# Sheet1.net
KiCad netlist of a schematic drawn in Altium Designer
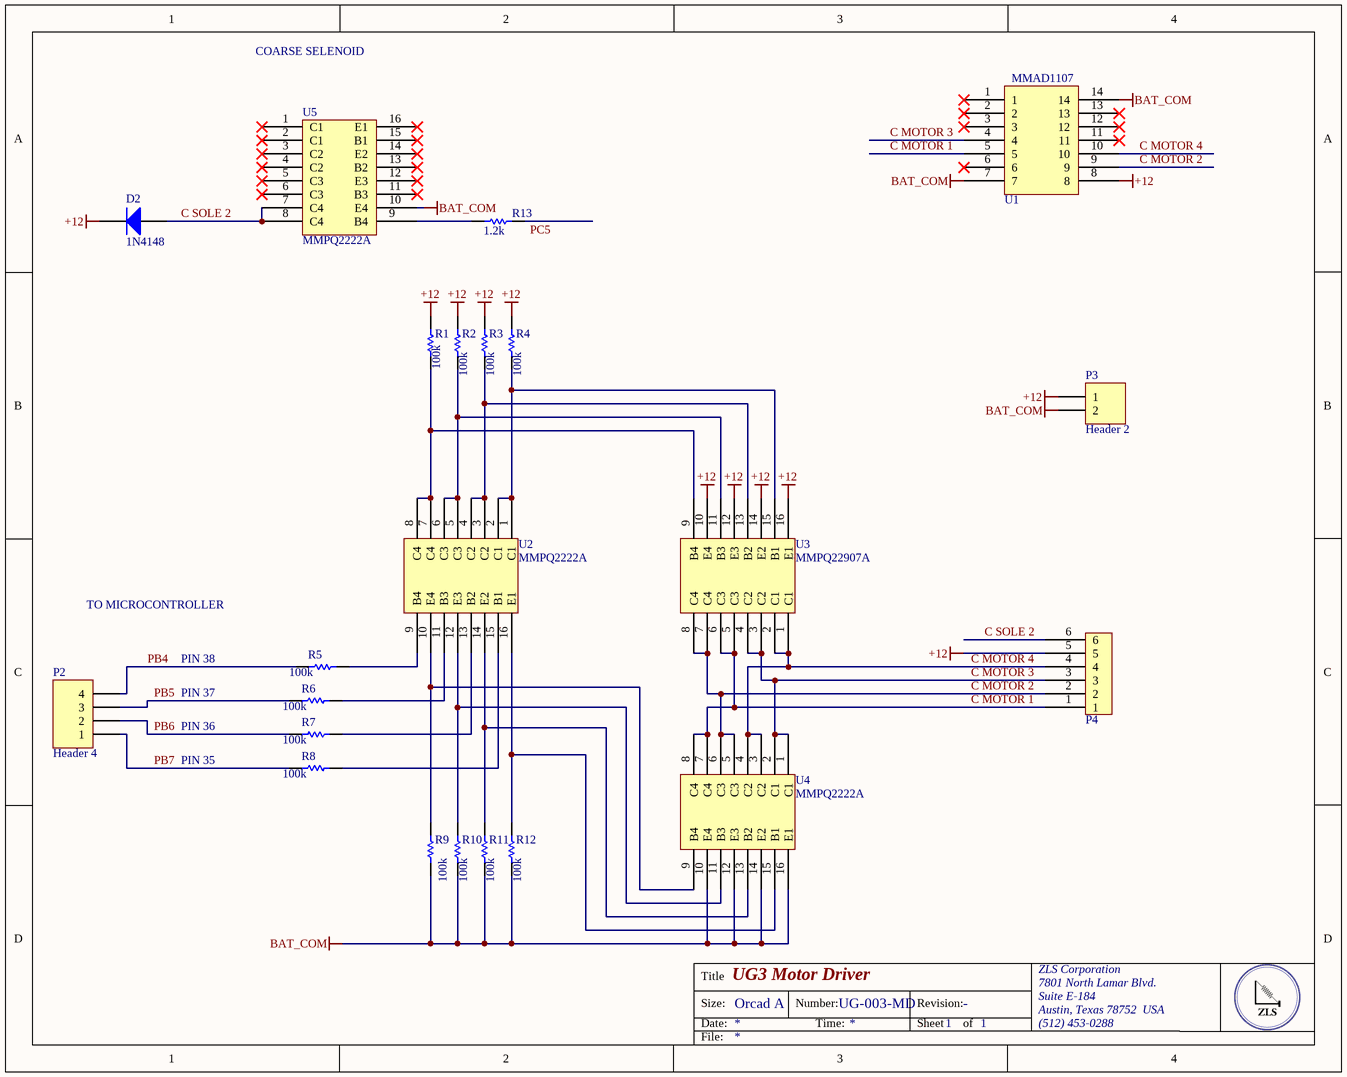
[diagram p0: Sheet1.SchDoc]

(export (version "E")
  (design (tool "Eeschema 10.0.6"))
  (components
    (comp (ref "D2")
      (value "1N4148")
      (footprint "NXP-SOD27-2_V")
      (description "High-speed Diode, 100 V, 450 mA, 2-Pin SOD27, RoHS")
      (fields (field (name "MANUFACTURER") "NXP Semiconductors"))
      (libsource (lib "Altium Content Vault") (part "NXP-A1K2-2"))
    )
    (comp (ref "P2")
      (value "Header 4")
      (footprint "HDR1X4")
      (description "Header, 4-Pin")
      (fields (field (name "PUBLISHER") "Altium Limited"))
      (libsource (lib "Miscellaneous Connectors") (part "Header 4"))
    )
    (comp (ref "P3")
      (value "Header 2")
      (footprint "HDR1X2")
      (description "Header, 2-Pin")
      (fields (field (name "PUBLISHER") "Altium Limited"))
      (libsource (lib "Miscellaneous Connectors") (part "Header 2"))
    )
    (comp (ref "P4") (value "JF-6") (footprint "JF-6") (libsource (lib "ZLS_Schematic_lib") (part "JF-6")))
    (comp (ref "R1")
      (value "100k")
      (footprint "RESC0805(2012)_L")
      (description "2R55 0.125W 1% 0805 (2012 Metric)  SMD")
      (fields (field (name "TOLERANCE") "1 %") (field (name "POWER") "0.125 W"))
      (libsource (lib "Altium Content Vault") (part "CMP-1013-00215-1"))
    )
    (comp (ref "R2")
      (value "100k")
      (footprint "RESC0805(2012)_L")
      (description "2R55 0.125W 1% 0805 (2012 Metric)  SMD")
      (fields (field (name "TOLERANCE") "1 %") (field (name "POWER") "0.125 W"))
      (libsource (lib "Altium Content Vault") (part "CMP-1013-00215-1"))
    )
    (comp (ref "R3")
      (value "100k")
      (footprint "RESC0805(2012)_L")
      (description "2R55 0.125W 1% 0805 (2012 Metric)  SMD")
      (fields (field (name "TOLERANCE") "1 %") (field (name "POWER") "0.125 W"))
      (libsource (lib "Altium Content Vault") (part "CMP-1013-00215-1"))
    )
    (comp (ref "R4")
      (value "100k")
      (footprint "RESC0805(2012)_L")
      (description "2R55 0.125W 1% 0805 (2012 Metric)  SMD")
      (fields (field (name "TOLERANCE") "1 %") (field (name "POWER") "0.125 W"))
      (libsource (lib "Altium Content Vault") (part "CMP-1013-00215-1"))
    )
    (comp (ref "R5")
      (value "100k")
      (footprint "RESC0805(2012)_L")
      (description "2R55 0.125W 1% 0805 (2012 Metric)  SMD")
      (fields (field (name "TOLERANCE") "1 %") (field (name "POWER") "0.125 W"))
      (libsource (lib "Altium Content Vault") (part "CMP-1013-00215-1"))
    )
    (comp (ref "R6")
      (value "100k")
      (footprint "RESC0805(2012)_L")
      (description "2R55 0.125W 1% 0805 (2012 Metric)  SMD")
      (fields (field (name "TOLERANCE") "1 %") (field (name "POWER") "0.125 W"))
      (libsource (lib "Altium Content Vault") (part "CMP-1013-00215-1"))
    )
    (comp (ref "R7")
      (value "100k")
      (footprint "RESC0805(2012)_L")
      (description "2R55 0.125W 1% 0805 (2012 Metric)  SMD")
      (fields (field (name "TOLERANCE") "1 %") (field (name "POWER") "0.125 W"))
      (libsource (lib "Altium Content Vault") (part "CMP-1013-00215-1"))
    )
    (comp (ref "R8")
      (value "100k")
      (footprint "RESC0805(2012)_L")
      (description "2R55 0.125W 1% 0805 (2012 Metric)  SMD")
      (fields (field (name "TOLERANCE") "1 %") (field (name "POWER") "0.125 W"))
      (libsource (lib "Altium Content Vault") (part "CMP-1013-00215-1"))
    )
    (comp (ref "R9")
      (value "100k")
      (footprint "RESC0805(2012)_L")
      (description "2R55 0.125W 1% 0805 (2012 Metric)  SMD")
      (fields (field (name "TOLERANCE") "1 %") (field (name "POWER") "0.125 W"))
      (libsource (lib "Altium Content Vault") (part "CMP-1013-00215-1"))
    )
    (comp (ref "R10")
      (value "100k")
      (footprint "RESC0805(2012)_L")
      (description "2R55 0.125W 1% 0805 (2012 Metric)  SMD")
      (fields (field (name "TOLERANCE") "1 %") (field (name "POWER") "0.125 W"))
      (libsource (lib "Altium Content Vault") (part "CMP-1013-00215-1"))
    )
    (comp (ref "R11")
      (value "100k")
      (footprint "RESC0805(2012)_L")
      (description "2R55 0.125W 1% 0805 (2012 Metric)  SMD")
      (fields (field (name "TOLERANCE") "1 %") (field (name "POWER") "0.125 W"))
      (libsource (lib "Altium Content Vault") (part "CMP-1013-00215-1"))
    )
    (comp (ref "R12")
      (value "100k")
      (footprint "RESC0805(2012)_L")
      (description "2R55 0.125W 1% 0805 (2012 Metric)  SMD")
      (fields (field (name "TOLERANCE") "1 %") (field (name "POWER") "0.125 W"))
      (libsource (lib "Altium Content Vault") (part "CMP-1013-00215-1"))
    )
    (comp (ref "R13")
      (value "1.2k")
      (footprint "RESC0805(2012)_L")
      (description "2R55 0.125W 1% 0805 (2012 Metric)  SMD")
      (fields (field (name "TOLERANCE") "1 %") (field (name "POWER") "0.125 W"))
      (libsource (lib "Altium Content Vault") (part "CMP-1013-00215-1"))
    )
    (comp (ref "U1")
      (value "MMAD1107")
      (footprint "MMAD1107")
      (libsource (lib "ZLS_Schematic_lib") (part "MMAD1107"))
    )
    (comp (ref "U2")
      (value "MMPQ2222A")
      (footprint "MMPQ2222A")
      (libsource (lib "ZLS_Schematic_lib") (part "MMPQ2222A"))
    )
    (comp (ref "U3")
      (value "MMPQ22907A")
      (footprint "MMPQ22907A")
      (libsource (lib "ZLS_Schematic_lib") (part "MMPQ22907A"))
    )
    (comp (ref "U4")
      (value "MMPQ2222A")
      (footprint "MMPQ2222A")
      (libsource (lib "ZLS_Schematic_lib") (part "MMPQ2222A"))
    )
    (comp (ref "U5") (value "MMPQ2222A") (footprint "MMPQ2222A") (libsource (lib "") (part "MMPQ2222A_1")))
  )
  (nets
    (net (code "1") (name "+12") (class "Default")
      (node (ref "D2") (pin "2") (pinfunction "K_2") (pintype "passive"))
      (node (ref "P3") (pin "1") (pinfunction "1_1") (pintype "passive"))
      (node (ref "P4") (pin "5") (pinfunction "5_5") (pintype "passive"))
      (node (ref "R1") (pin "1") (pinfunction "1_1") (pintype "passive"))
      (node (ref "R2") (pin "1") (pinfunction "1_1") (pintype "passive"))
      (node (ref "R3") (pin "1") (pinfunction "1_1") (pintype "passive"))
      (node (ref "R4") (pin "1") (pinfunction "1_1") (pintype "passive"))
      (node (ref "U1") (pin "8") (pinfunction "8_8") (pintype "passive"))
      (node (ref "U3") (pin "10") (pinfunction "E4_10") (pintype "passive"))
      (node (ref "U3") (pin "12") (pinfunction "E3_12") (pintype "passive"))
      (node (ref "U3") (pin "14") (pinfunction "E2_14") (pintype "passive"))
      (node (ref "U3") (pin "16") (pinfunction "E1_16") (pintype "passive"))
    )
    (net (code "2") (name "/C MOTOR 1") (class "Default")
      (node (ref "P4") (pin "1") (pinfunction "1_1") (pintype "passive"))
      (node (ref "U1") (pin "5") (pinfunction "5_5") (pintype "passive"))
      (node (ref "U3") (pin "5") (pinfunction "C3_5") (pintype "passive"))
      (node (ref "U3") (pin "6") (pinfunction "C3_6") (pintype "passive"))
      (node (ref "U4") (pin "7") (pinfunction "C4_7") (pintype "passive"))
      (node (ref "U4") (pin "8") (pinfunction "C4_8") (pintype "passive"))
    )
    (net (code "3") (name "/C MOTOR 2") (class "Default")
      (node (ref "P4") (pin "2") (pinfunction "2_2") (pintype "passive"))
      (node (ref "U1") (pin "9") (pinfunction "9_9") (pintype "passive"))
      (node (ref "U3") (pin "7") (pinfunction "C4_7") (pintype "passive"))
      (node (ref "U3") (pin "8") (pinfunction "C4_8") (pintype "passive"))
      (node (ref "U4") (pin "5") (pinfunction "C3_5") (pintype "passive"))
      (node (ref "U4") (pin "6") (pinfunction "C3_6") (pintype "passive"))
    )
    (net (code "4") (name "/C MOTOR 3") (class "Default")
      (node (ref "P4") (pin "3") (pinfunction "3_3") (pintype "passive"))
      (node (ref "U1") (pin "4") (pinfunction "4_4") (pintype "passive"))
      (node (ref "U3") (pin "3") (pinfunction "C2_3") (pintype "passive"))
      (node (ref "U3") (pin "4") (pinfunction "C2_4") (pintype "passive"))
      (node (ref "U4") (pin "1") (pinfunction "C1_1") (pintype "passive"))
      (node (ref "U4") (pin "2") (pinfunction "C1_2") (pintype "passive"))
    )
    (net (code "5") (name "/C MOTOR 4") (class "Default")
      (node (ref "P4") (pin "4") (pinfunction "4_4") (pintype "passive"))
      (node (ref "U1") (pin "10") (pinfunction "10_10") (pintype "passive"))
      (node (ref "U3") (pin "1") (pinfunction "C1_1") (pintype "passive"))
      (node (ref "U3") (pin "2") (pinfunction "C1_2") (pintype "passive"))
      (node (ref "U4") (pin "3") (pinfunction "C2_3") (pintype "passive"))
      (node (ref "U4") (pin "4") (pinfunction "C2_4") (pintype "passive"))
    )
    (net (code "6") (name "/C SOLE 2") (class "Default")
      (node (ref "D2") (pin "1") (pinfunction "A_1") (pintype "passive"))
      (node (ref "P4") (pin "6") (pinfunction "6_6") (pintype "passive"))
      (node (ref "U5") (pin "7") (pinfunction "C4_7") (pintype "passive"))
      (node (ref "U5") (pin "8") (pinfunction "C4_8") (pintype "passive"))
    )
    (net (code "7") (name "/PB4") (class "Default")
      (node (ref "P2") (pin "4") (pinfunction "4_4") (pintype "passive"))
      (node (ref "R5") (pin "2") (pinfunction "2_2") (pintype "passive"))
    )
    (net (code "8") (name "/PB5") (class "Default")
      (node (ref "P2") (pin "3") (pinfunction "3_3") (pintype "passive"))
      (node (ref "R6") (pin "2") (pinfunction "2_2") (pintype "passive"))
    )
    (net (code "9") (name "/PB6") (class "Default")
      (node (ref "P2") (pin "2") (pinfunction "2_2") (pintype "passive"))
      (node (ref "R7") (pin "2") (pinfunction "2_2") (pintype "passive"))
    )
    (net (code "10") (name "/PB7") (class "Default")
      (node (ref "P2") (pin "1") (pinfunction "1_1") (pintype "passive"))
      (node (ref "R8") (pin "2") (pinfunction "2_2") (pintype "passive"))
    )
    (net (code "11") (name "/PC5") (class "Default")
      (node (ref "R13") (pin "2") (pinfunction "2_2") (pintype "passive"))
    )
    (net (code "12") (name "BAT_COM") (class "Default")
      (node (ref "P3") (pin "2") (pinfunction "2_2") (pintype "passive"))
      (node (ref "R10") (pin "1") (pinfunction "1_1") (pintype "passive"))
      (node (ref "R11") (pin "1") (pinfunction "1_1") (pintype "passive"))
      (node (ref "R12") (pin "1") (pinfunction "1_1") (pintype "passive"))
      (node (ref "R9") (pin "1") (pinfunction "1_1") (pintype "passive"))
      (node (ref "U1") (pin "14") (pinfunction "14_14") (pintype "passive"))
      (node (ref "U1") (pin "7") (pinfunction "7_7") (pintype "passive"))
      (node (ref "U4") (pin "10") (pinfunction "E4_10") (pintype "passive"))
      (node (ref "U4") (pin "12") (pinfunction "E3_12") (pintype "passive"))
      (node (ref "U4") (pin "14") (pinfunction "E2_14") (pintype "passive"))
      (node (ref "U4") (pin "16") (pinfunction "E1_16") (pintype "passive"))
      (node (ref "U5") (pin "10") (pinfunction "E4_10") (pintype "passive"))
    )
    (net (code "13") (name "Net-(U2-B1)") (class "Default")
      (node (ref "R8") (pin "1") (pinfunction "1_1") (pintype "passive"))
      (node (ref "U2") (pin "15") (pinfunction "B1_15") (pintype "passive"))
    )
    (net (code "14") (name "Net-(U2-B2)") (class "Default")
      (node (ref "R7") (pin "1") (pinfunction "1_1") (pintype "passive"))
      (node (ref "U2") (pin "13") (pinfunction "B2_13") (pintype "passive"))
    )
    (net (code "15") (name "Net-(U2-B3)") (class "Default")
      (node (ref "R6") (pin "1") (pinfunction "1_1") (pintype "passive"))
      (node (ref "U2") (pin "11") (pinfunction "B3_11") (pintype "passive"))
    )
    (net (code "16") (name "Net-(U2-B4)") (class "Default")
      (node (ref "R5") (pin "1") (pinfunction "1_1") (pintype "passive"))
      (node (ref "U2") (pin "9") (pinfunction "B4_9") (pintype "passive"))
    )
    (net (code "17") (name "Net-(U2-E1)") (class "Default")
      (node (ref "R12") (pin "2") (pinfunction "2_2") (pintype "passive"))
      (node (ref "U2") (pin "16") (pinfunction "E1_16") (pintype "passive"))
      (node (ref "U4") (pin "15") (pinfunction "B1_15") (pintype "passive"))
    )
    (net (code "18") (name "Net-(U2-E2)") (class "Default")
      (node (ref "R11") (pin "2") (pinfunction "2_2") (pintype "passive"))
      (node (ref "U2") (pin "14") (pinfunction "E2_14") (pintype "passive"))
      (node (ref "U4") (pin "13") (pinfunction "B2_13") (pintype "passive"))
    )
    (net (code "19") (name "Net-(U2-E3)") (class "Default")
      (node (ref "R10") (pin "2") (pinfunction "2_2") (pintype "passive"))
      (node (ref "U2") (pin "12") (pinfunction "E3_12") (pintype "passive"))
      (node (ref "U4") (pin "11") (pinfunction "B3_11") (pintype "passive"))
    )
    (net (code "20") (name "Net-(U2-E4)") (class "Default")
      (node (ref "R9") (pin "2") (pinfunction "2_2") (pintype "passive"))
      (node (ref "U2") (pin "10") (pinfunction "E4_10") (pintype "passive"))
      (node (ref "U4") (pin "9") (pinfunction "B4_9") (pintype "passive"))
    )
    (net (code "21") (name "Net-(U3-B1)") (class "Default")
      (node (ref "R4") (pin "2") (pinfunction "2_2") (pintype "passive"))
      (node (ref "U2") (pin "1") (pinfunction "C1_1") (pintype "passive"))
      (node (ref "U2") (pin "2") (pinfunction "C1_2") (pintype "passive"))
      (node (ref "U3") (pin "15") (pinfunction "B1_15") (pintype "passive"))
    )
    (net (code "22") (name "Net-(U3-B2)") (class "Default")
      (node (ref "R3") (pin "2") (pinfunction "2_2") (pintype "passive"))
      (node (ref "U2") (pin "3") (pinfunction "C2_3") (pintype "passive"))
      (node (ref "U2") (pin "4") (pinfunction "C2_4") (pintype "passive"))
      (node (ref "U3") (pin "13") (pinfunction "B2_13") (pintype "passive"))
    )
    (net (code "23") (name "Net-(U3-B3)") (class "Default")
      (node (ref "R2") (pin "2") (pinfunction "2_2") (pintype "passive"))
      (node (ref "U2") (pin "5") (pinfunction "C3_5") (pintype "passive"))
      (node (ref "U2") (pin "6") (pinfunction "C3_6") (pintype "passive"))
      (node (ref "U3") (pin "11") (pinfunction "B3_11") (pintype "passive"))
    )
    (net (code "24") (name "Net-(U3-B4)") (class "Default")
      (node (ref "R1") (pin "2") (pinfunction "2_2") (pintype "passive"))
      (node (ref "U2") (pin "7") (pinfunction "C4_7") (pintype "passive"))
      (node (ref "U2") (pin "8") (pinfunction "C4_8") (pintype "passive"))
      (node (ref "U3") (pin "9") (pinfunction "B4_9") (pintype "passive"))
    )
    (net (code "25") (name "Net-(U5-B4)") (class "Default")
      (node (ref "R13") (pin "1") (pinfunction "1_1") (pintype "passive"))
      (node (ref "U5") (pin "9") (pinfunction "B4_9") (pintype "passive"))
    )
    (net (code "26") (name "unconnected-(U1-Pad1)") (class "Default")
      (node (ref "U1") (pin "1") (pinfunction "1_1") (pintype "passive+no_connect"))
    )
    (net (code "27") (name "unconnected-(U1-Pad2)") (class "Default")
      (node (ref "U1") (pin "2") (pinfunction "2_2") (pintype "passive+no_connect"))
    )
    (net (code "28") (name "unconnected-(U1-Pad3)") (class "Default")
      (node (ref "U1") (pin "3") (pinfunction "3_3") (pintype "passive+no_connect"))
    )
    (net (code "29") (name "unconnected-(U1-Pad6)") (class "Default")
      (node (ref "U1") (pin "6") (pinfunction "6_6") (pintype "passive+no_connect"))
    )
    (net (code "30") (name "unconnected-(U1-Pad11)") (class "Default")
      (node (ref "U1") (pin "11") (pinfunction "11_11") (pintype "passive+no_connect"))
    )
    (net (code "31") (name "unconnected-(U1-Pad12)") (class "Default")
      (node (ref "U1") (pin "12") (pinfunction "12_12") (pintype "passive+no_connect"))
    )
    (net (code "32") (name "unconnected-(U1-Pad13)") (class "Default")
      (node (ref "U1") (pin "13") (pinfunction "13_13") (pintype "passive+no_connect"))
    )
    (net (code "33") (name "unconnected-(U5-B1-Pad15)") (class "Default")
      (node (ref "U5") (pin "15") (pinfunction "B1_15") (pintype "passive+no_connect"))
    )
    (net (code "34") (name "unconnected-(U5-B2-Pad13)") (class "Default")
      (node (ref "U5") (pin "13") (pinfunction "B2_13") (pintype "passive+no_connect"))
    )
    (net (code "35") (name "unconnected-(U5-B3-Pad11)") (class "Default")
      (node (ref "U5") (pin "11") (pinfunction "B3_11") (pintype "passive+no_connect"))
    )
    (net (code "36") (name "unconnected-(U5-C1-Pad1)") (class "Default")
      (node (ref "U5") (pin "1") (pinfunction "C1_1") (pintype "passive+no_connect"))
    )
    (net (code "37") (name "unconnected-(U5-C1-Pad2)") (class "Default")
      (node (ref "U5") (pin "2") (pinfunction "C1_2") (pintype "passive+no_connect"))
    )
    (net (code "38") (name "unconnected-(U5-C2-Pad3)") (class "Default")
      (node (ref "U5") (pin "3") (pinfunction "C2_3") (pintype "passive+no_connect"))
    )
    (net (code "39") (name "unconnected-(U5-C2-Pad4)") (class "Default")
      (node (ref "U5") (pin "4") (pinfunction "C2_4") (pintype "passive+no_connect"))
    )
    (net (code "40") (name "unconnected-(U5-C3-Pad5)") (class "Default")
      (node (ref "U5") (pin "5") (pinfunction "C3_5") (pintype "passive+no_connect"))
    )
    (net (code "41") (name "unconnected-(U5-C3-Pad6)") (class "Default")
      (node (ref "U5") (pin "6") (pinfunction "C3_6") (pintype "passive+no_connect"))
    )
    (net (code "42") (name "unconnected-(U5-E1-Pad16)") (class "Default")
      (node (ref "U5") (pin "16") (pinfunction "E1_16") (pintype "passive+no_connect"))
    )
    (net (code "43") (name "unconnected-(U5-E2-Pad14)") (class "Default")
      (node (ref "U5") (pin "14") (pinfunction "E2_14") (pintype "passive+no_connect"))
    )
    (net (code "44") (name "unconnected-(U5-E3-Pad12)") (class "Default")
      (node (ref "U5") (pin "12") (pinfunction "E3_12") (pintype "passive+no_connect"))
    )
  )
)
